# WBH2.net
KiCad netlist of a schematic drawn in EAGLE
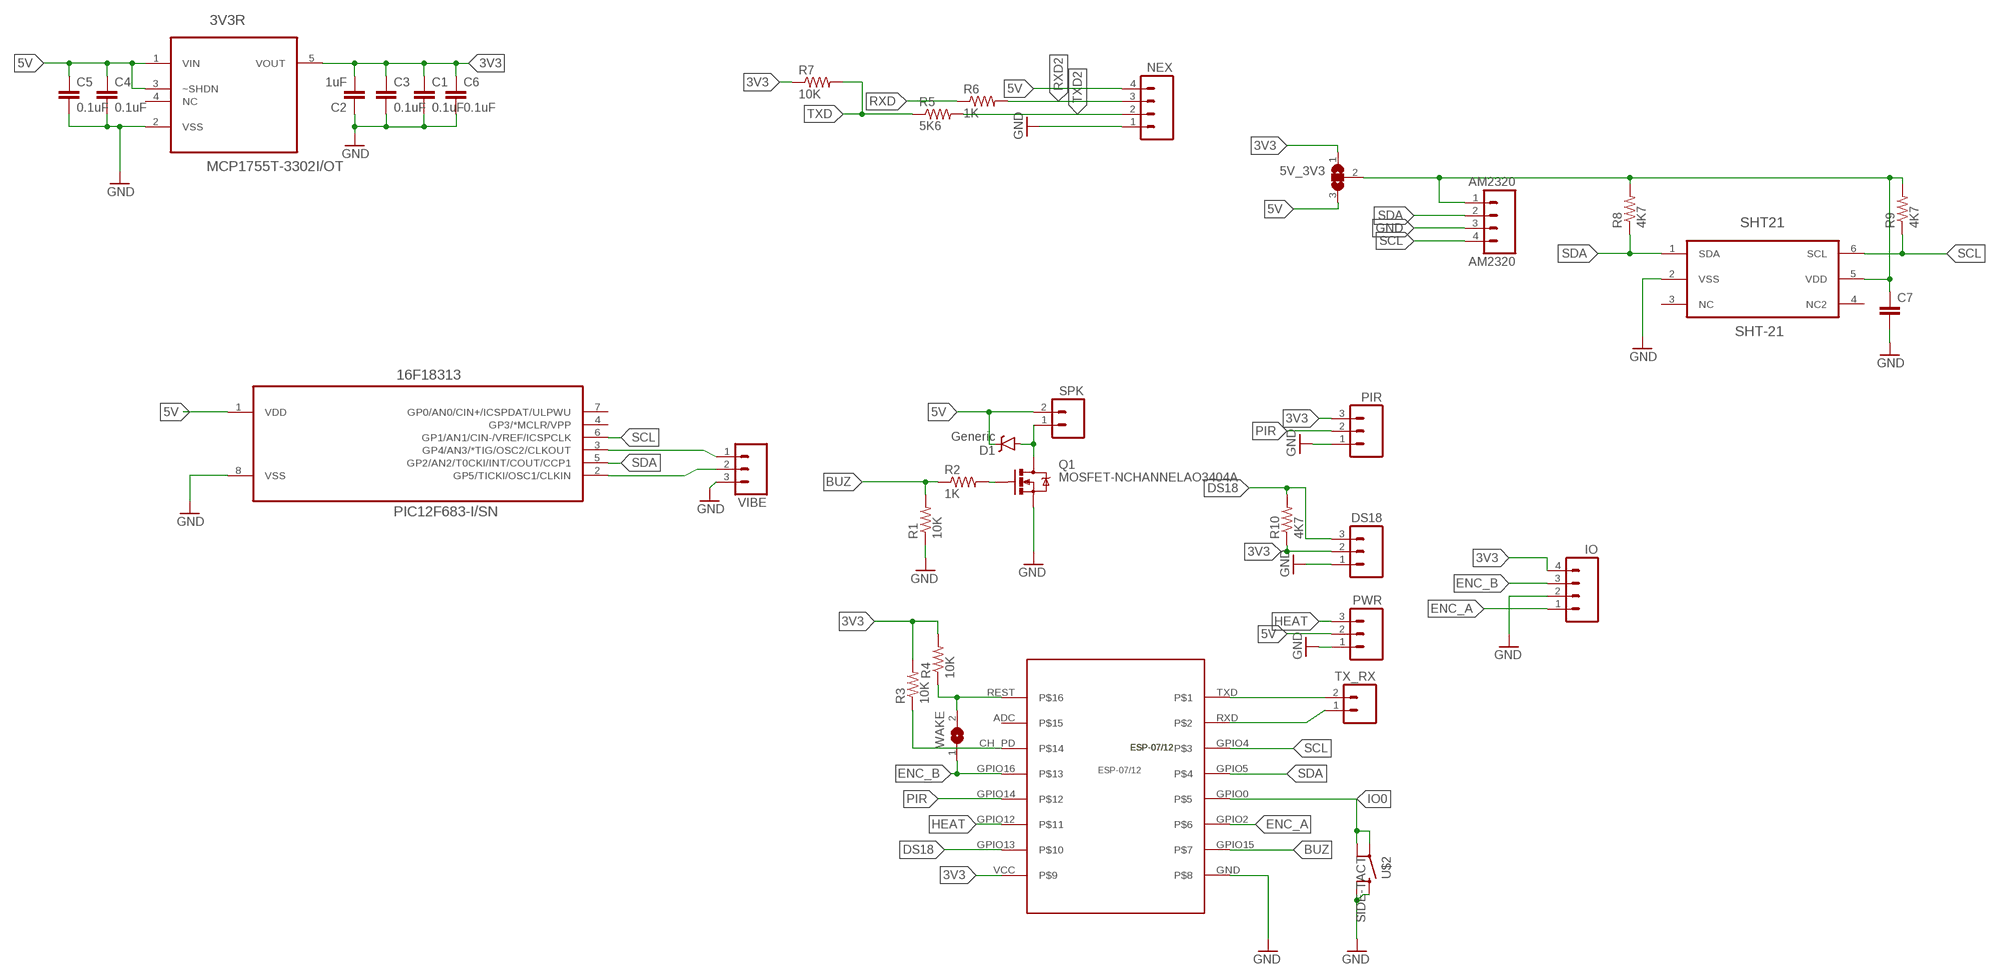
[diagram p0: schematic, sheet 1]

(export (version "E")
  (design (tool "Eeschema 10.0.6"))
  (components
    (comp (ref "3V3R")
      (value "MCP1755T-3302I/OT")
      (footprint "eagle-import:SOT95P270X145-5N")
      (fields (field (name "MPN") "MCP1801T-3302I/OT"))
      (libsource (lib "eagle-import") (part "MCP1801T-3302I/OT"))
    )
    (comp (ref "5V_3V3")
      (value "SJ2W")
      (footprint "eagle-import:SJ_2")
      (libsource (lib "eagle-import") (part "SJ2W"))
    )
    (comp (ref "16F18313")
      (value "PIC12F683-I/SN")
      (footprint "eagle-import:SOIC127P600X175-8N")
      (libsource (lib "eagle-import") (part "PIC12F683-I/SN"))
    )
    (comp (ref "AM2320")
      (value "AM2320")
      (footprint "eagle-import:1X04")
      (libsource (lib "eagle-import") (part "M04PTH"))
    )
    (comp (ref "C1")
      (value "0.1uF")
      (footprint "eagle-import:0805")
      (libsource (lib "eagle-import") (part "CAP0805"))
    )
    (comp (ref "C2")
      (value "1uF")
      (footprint "eagle-import:0805")
      (libsource (lib "eagle-import") (part "CAP0805"))
    )
    (comp (ref "C3")
      (value "0.1uF")
      (footprint "eagle-import:0805")
      (libsource (lib "eagle-import") (part "CAP0805"))
    )
    (comp (ref "C4")
      (value "0.1uF")
      (footprint "eagle-import:0805")
      (libsource (lib "eagle-import") (part "CAP0805"))
    )
    (comp (ref "C5")
      (value "0.1uF")
      (footprint "eagle-import:0805")
      (libsource (lib "eagle-import") (part "CAP0805"))
    )
    (comp (ref "C6")
      (value "0.1uF")
      (footprint "eagle-import:0805")
      (libsource (lib "eagle-import") (part "CAP0805"))
    )
    (comp (ref "C7")
      (value "CAP0603-CAP")
      (footprint "eagle-import:0603-CAP")
      (libsource (lib "eagle-import") (part "CAP0603-CAP"))
    )
    (comp (ref "D1")
      (value "Generic")
      (footprint "eagle-import:SOD-323")
      (libsource (lib "eagle-import") (part "DIODE-SCHOTTKY-BAT20J"))
    )
    (comp (ref "DS18")
      (value "M03PTH")
      (footprint "eagle-import:1X03")
      (libsource (lib "eagle-import") (part "M03PTH"))
    )
    (comp (ref "IO")
      (value "M04PTH")
      (footprint "eagle-import:1X04")
      (libsource (lib "eagle-import") (part "M04PTH"))
    )
    (comp (ref "NEX")
      (value "M04PTH")
      (footprint "eagle-import:1X04")
      (libsource (lib "eagle-import") (part "M04PTH"))
    )
    (comp (ref "PIR")
      (value "M03PTH")
      (footprint "eagle-import:1X03")
      (libsource (lib "eagle-import") (part "M03PTH"))
    )
    (comp (ref "PWR")
      (value "M03PTH")
      (footprint "eagle-import:1X03")
      (libsource (lib "eagle-import") (part "M03PTH"))
    )
    (comp (ref "Q1")
      (value "MOSFET-NCHANNELAO3404A")
      (footprint "eagle-import:SOT23-3")
      (libsource (lib "eagle-import") (part "MOSFET-NCHANNELAO3404A"))
    )
    (comp (ref "R1")
      (value "10K")
      (footprint "eagle-import:0805")
      (libsource (lib "eagle-import") (part "RESISTOR0805-RES"))
    )
    (comp (ref "R2")
      (value "1K")
      (footprint "eagle-import:0805")
      (libsource (lib "eagle-import") (part "RESISTOR0805-RES"))
    )
    (comp (ref "R3")
      (value "10K")
      (footprint "eagle-import:0805")
      (libsource (lib "eagle-import") (part "RESISTOR0805-RES"))
    )
    (comp (ref "R4")
      (value "10K")
      (footprint "eagle-import:0805")
      (libsource (lib "eagle-import") (part "RESISTOR0805-RES"))
    )
    (comp (ref "R5")
      (value "5K6")
      (footprint "eagle-import:0805")
      (libsource (lib "eagle-import") (part "RESISTOR0805-RES"))
    )
    (comp (ref "R6")
      (value "1K")
      (footprint "eagle-import:0805")
      (libsource (lib "eagle-import") (part "RESISTOR0805-RES"))
    )
    (comp (ref "R7")
      (value "10K")
      (footprint "eagle-import:0805")
      (libsource (lib "eagle-import") (part "RESISTOR0805-RES"))
    )
    (comp (ref "R8")
      (value "4K7")
      (footprint "eagle-import:0805")
      (libsource (lib "eagle-import") (part "RESISTOR0805-RES"))
    )
    (comp (ref "R9")
      (value "4K7")
      (footprint "eagle-import:0805")
      (libsource (lib "eagle-import") (part "RESISTOR0805-RES"))
    )
    (comp (ref "R10")
      (value "4K7")
      (footprint "eagle-import:0805")
      (libsource (lib "eagle-import") (part "RESISTOR0805-RES"))
    )
    (comp (ref "SHT21")
      (value "SHT-21")
      (footprint "eagle-import:SHT21")
      (libsource (lib "eagle-import") (part "SHT-21"))
    )
    (comp (ref "SPK")
      (value "M02PTH")
      (footprint "eagle-import:1X02")
      (libsource (lib "eagle-import") (part "M02PTH"))
    )
    (comp (ref "TX_RX")
      (value "M02PTH")
      (footprint "eagle-import:1X02")
      (libsource (lib "eagle-import") (part "M02PTH"))
    )
    (comp (ref "U$1")
      (value "ESP-07/12")
      (footprint "eagle-import:ESP-07_12")
      (libsource (lib "eagle-import") (part "ESP-07/12"))
    )
    (comp (ref "U$2")
      (value "SIDE-TACT")
      (footprint "eagle-import:SIDE-TACT")
      (libsource (lib "eagle-import") (part "SIDE-TACT"))
    )
    (comp (ref "VIBE")
      (value "M03PTH")
      (footprint "eagle-import:1X03")
      (libsource (lib "eagle-import") (part "M03PTH"))
    )
    (comp (ref "WAKE")
      (value "SJ")
      (footprint "eagle-import:SJ")
      (libsource (lib "eagle-import") (part "SJ"))
    )
  )
  (nets
    (net (code "1") (name "/NC") (class "Default")
      (node (ref "SHT21") (pin "3") (pinfunction "NC_3") (pintype "power_in"))
    )
    (net (code "2") (name "3V3") (class "Default")
      (node (ref "3V3R") (pin "5") (pinfunction "VOUT_5") (pintype "output"))
      (node (ref "5V_3V3") (pin "1") (pinfunction "1_1") (pintype "passive"))
      (node (ref "C1") (pin "1") (pinfunction "1_1") (pintype "passive"))
      (node (ref "C2") (pin "2") (pinfunction "2_2") (pintype "passive"))
      (node (ref "C3") (pin "1") (pinfunction "1_1") (pintype "passive"))
      (node (ref "C6") (pin "1") (pinfunction "1_1") (pintype "passive"))
      (node (ref "DS18") (pin "2") (pinfunction "2_2") (pintype "passive"))
      (node (ref "IO") (pin "4") (pinfunction "4_4") (pintype "passive"))
      (node (ref "PIR") (pin "3") (pinfunction "3_3") (pintype "passive"))
      (node (ref "R10") (pin "1") (pinfunction "1_1") (pintype "passive"))
      (node (ref "R3") (pin "2") (pinfunction "2_2") (pintype "passive"))
      (node (ref "R4") (pin "2") (pinfunction "2_2") (pintype "passive"))
      (node (ref "R7") (pin "1") (pinfunction "1_1") (pintype "passive"))
      (node (ref "U$1") (pin "VCC") (pinfunction "P$9_VCC") (pintype "bidirectional"))
    )
    (net (code "3") (name "5V") (class "Default")
      (node (ref "16F18313") (pin "1") (pinfunction "VDD_1") (pintype "power_in"))
      (node (ref "3V3R") (pin "1") (pinfunction "VIN_1") (pintype "power_in"))
      (node (ref "3V3R") (pin "3") (pinfunction "~{SHDN}_3") (pintype "input"))
      (node (ref "5V_3V3") (pin "3") (pinfunction "3_3") (pintype "passive"))
      (node (ref "C4") (pin "1") (pinfunction "1_1") (pintype "passive"))
      (node (ref "C5") (pin "1") (pinfunction "1_1") (pintype "passive"))
      (node (ref "D1") (pin "C") (pinfunction "C_C") (pintype "passive"))
      (node (ref "NEX") (pin "4") (pinfunction "4_4") (pintype "passive"))
      (node (ref "PWR") (pin "2") (pinfunction "2_2") (pintype "passive"))
      (node (ref "SPK") (pin "2") (pinfunction "2_2") (pintype "passive"))
    )
    (net (code "4") (name "BUZ") (class "Default")
      (node (ref "R1") (pin "2") (pinfunction "2_2") (pintype "passive"))
      (node (ref "R2") (pin "1") (pinfunction "1_1") (pintype "passive"))
      (node (ref "U$1") (pin "GPIO15") (pinfunction "P$7_GPIO15") (pintype "bidirectional"))
    )
    (net (code "5") (name "DS18") (class "Default")
      (node (ref "DS18") (pin "3") (pinfunction "3_3") (pintype "passive"))
      (node (ref "R10") (pin "2") (pinfunction "2_2") (pintype "passive"))
      (node (ref "U$1") (pin "GPIO13") (pinfunction "P$10_GPIO13") (pintype "bidirectional"))
    )
    (net (code "6") (name "ENC_A") (class "Default")
      (node (ref "IO") (pin "1") (pinfunction "1_1") (pintype "passive"))
      (node (ref "U$1") (pin "GPIO2") (pinfunction "P$6_GPIO2") (pintype "bidirectional"))
    )
    (net (code "7") (name "ENC_B") (class "Default")
      (node (ref "IO") (pin "3") (pinfunction "3_3") (pintype "passive"))
      (node (ref "U$1") (pin "GPIO16") (pinfunction "P$13_GPIO16") (pintype "bidirectional"))
      (node (ref "WAKE") (pin "1") (pinfunction "1_1") (pintype "passive"))
    )
    (net (code "8") (name "GND") (class "Default")
      (node (ref "16F18313") (pin "8") (pinfunction "VSS_8") (pintype "passive"))
      (node (ref "3V3R") (pin "2") (pinfunction "VSS_2") (pintype "passive"))
      (node (ref "AM2320") (pin "3") (pinfunction "3_3") (pintype "passive"))
      (node (ref "C1") (pin "2") (pinfunction "2_2") (pintype "passive"))
      (node (ref "C2") (pin "1") (pinfunction "1_1") (pintype "passive"))
      (node (ref "C3") (pin "2") (pinfunction "2_2") (pintype "passive"))
      (node (ref "C4") (pin "2") (pinfunction "2_2") (pintype "passive"))
      (node (ref "C5") (pin "2") (pinfunction "2_2") (pintype "passive"))
      (node (ref "C6") (pin "2") (pinfunction "2_2") (pintype "passive"))
      (node (ref "C7") (pin "2") (pinfunction "2_2") (pintype "passive"))
      (node (ref "DS18") (pin "1") (pinfunction "1_1") (pintype "passive"))
      (node (ref "IO") (pin "2") (pinfunction "2_2") (pintype "passive"))
      (node (ref "NEX") (pin "1") (pinfunction "1_1") (pintype "passive"))
      (node (ref "PIR") (pin "1") (pinfunction "1_1") (pintype "passive"))
      (node (ref "PWR") (pin "1") (pinfunction "1_1") (pintype "passive"))
      (node (ref "Q1") (pin "2") (pinfunction "S_2") (pintype "passive"))
      (node (ref "R1") (pin "1") (pinfunction "1_1") (pintype "passive"))
      (node (ref "SHT21") (pin "2") (pinfunction "VSS_2") (pintype "input"))
      (node (ref "U$1") (pin "GND") (pinfunction "P$8_GND") (pintype "bidirectional"))
      (node (ref "U$2") (pin "3") (pinfunction "2_3") (pintype "passive"))
      (node (ref "U$2") (pin "4") (pinfunction "4_4") (pintype "passive"))
      (node (ref "VIBE") (pin "3") (pinfunction "3_3") (pintype "passive"))
    )
    (net (code "9") (name "HEAT") (class "Default")
      (node (ref "PWR") (pin "3") (pinfunction "3_3") (pintype "passive"))
      (node (ref "U$1") (pin "GPIO12") (pinfunction "P$11_GPIO12") (pintype "bidirectional"))
    )
    (net (code "10") (name "IO0") (class "Default")
      (node (ref "U$1") (pin "GPIO0") (pinfunction "P$5_GPIO0") (pintype "bidirectional"))
      (node (ref "U$2") (pin "1") (pinfunction "1_1") (pintype "passive"))
      (node (ref "U$2") (pin "2") (pinfunction "3_2") (pintype "passive"))
    )
    (net (code "11") (name "Net-(16F18313-GP4{slash}AN3{slash}*TIG{slash}OSC2{slash}CLKOUT)") (class "Default")
      (node (ref "16F18313") (pin "3") (pinfunction "GP4/AN3/*TIG/OSC2/CLKOUT_3") (pintype "bidirectional"))
      (node (ref "VIBE") (pin "1") (pinfunction "1_1") (pintype "passive"))
    )
    (net (code "12") (name "Net-(16F18313-GP5{slash}TICKI{slash}OSC1{slash}CLKIN)") (class "Default")
      (node (ref "16F18313") (pin "2") (pinfunction "GP5/TICKI/OSC1/CLKIN_2") (pintype "bidirectional"))
      (node (ref "VIBE") (pin "2") (pinfunction "2_2") (pintype "passive"))
    )
    (net (code "13") (name "Net-(Q1-D)") (class "Default")
      (node (ref "D1") (pin "A") (pinfunction "A_A") (pintype "passive"))
      (node (ref "Q1") (pin "3") (pinfunction "D_3") (pintype "passive"))
      (node (ref "SPK") (pin "1") (pinfunction "1_1") (pintype "passive"))
    )
    (net (code "14") (name "Net-(Q1-G)") (class "Default")
      (node (ref "Q1") (pin "1") (pinfunction "G_1") (pintype "passive"))
      (node (ref "R2") (pin "2") (pinfunction "2_2") (pintype "passive"))
    )
    (net (code "15") (name "Net-(SHT21-VDD)") (class "Default")
      (node (ref "5V_3V3") (pin "2") (pinfunction "2_2") (pintype "passive"))
      (node (ref "AM2320") (pin "1") (pinfunction "1_1") (pintype "passive"))
      (node (ref "C7") (pin "1") (pinfunction "1_1") (pintype "passive"))
      (node (ref "R8") (pin "2") (pinfunction "2_2") (pintype "passive"))
      (node (ref "R9") (pin "2") (pinfunction "2_2") (pintype "passive"))
      (node (ref "SHT21") (pin "5") (pinfunction "VDD_5") (pintype "bidirectional"))
    )
    (net (code "16") (name "Net-(U$1-P$14)") (class "Default")
      (node (ref "R3") (pin "1") (pinfunction "1_1") (pintype "passive"))
      (node (ref "U$1") (pin "CH_PD") (pinfunction "P$14_CH_PD") (pintype "bidirectional"))
    )
    (net (code "17") (name "Net-(U$1-P$16)") (class "Default")
      (node (ref "R4") (pin "1") (pinfunction "1_1") (pintype "passive"))
      (node (ref "U$1") (pin "REST") (pinfunction "P$16_REST") (pintype "bidirectional"))
      (node (ref "WAKE") (pin "2") (pinfunction "2_2") (pintype "passive"))
    )
    (net (code "18") (name "PIR") (class "Default")
      (node (ref "PIR") (pin "2") (pinfunction "2_2") (pintype "passive"))
      (node (ref "U$1") (pin "GPIO14") (pinfunction "P$12_GPIO14") (pintype "bidirectional"))
    )
    (net (code "19") (name "RXD") (class "Default")
      (node (ref "R6") (pin "1") (pinfunction "1_1") (pintype "passive"))
      (node (ref "TX_RX") (pin "1") (pinfunction "1_1") (pintype "passive"))
      (node (ref "U$1") (pin "RXD") (pinfunction "P$2_RXD") (pintype "bidirectional"))
    )
    (net (code "20") (name "RXD2") (class "Default")
      (node (ref "NEX") (pin "3") (pinfunction "3_3") (pintype "passive"))
      (node (ref "R6") (pin "2") (pinfunction "2_2") (pintype "passive"))
    )
    (net (code "21") (name "SCL") (class "Default")
      (node (ref "16F18313") (pin "6") (pinfunction "GP1/AN1/CIN-/VREF/ICSPCLK_6") (pintype "bidirectional"))
      (node (ref "AM2320") (pin "4") (pinfunction "4_4") (pintype "passive"))
      (node (ref "R9") (pin "1") (pinfunction "1_1") (pintype "passive"))
      (node (ref "SHT21") (pin "6") (pinfunction "SCL_6") (pintype "bidirectional"))
      (node (ref "U$1") (pin "GPIO4") (pinfunction "P$3_GPIO4") (pintype "bidirectional"))
    )
    (net (code "22") (name "SDA") (class "Default")
      (node (ref "16F18313") (pin "5") (pinfunction "GP2/AN2/T0CKI/INT/COUT/CCP1_5") (pintype "bidirectional"))
      (node (ref "AM2320") (pin "2") (pinfunction "2_2") (pintype "passive"))
      (node (ref "R8") (pin "1") (pinfunction "1_1") (pintype "passive"))
      (node (ref "SHT21") (pin "1") (pinfunction "SDA_1") (pintype "power_in"))
      (node (ref "U$1") (pin "GPIO5") (pinfunction "P$4_GPIO5") (pintype "bidirectional"))
    )
    (net (code "23") (name "TXD") (class "Default")
      (node (ref "R5") (pin "1") (pinfunction "1_1") (pintype "passive"))
      (node (ref "R7") (pin "2") (pinfunction "2_2") (pintype "passive"))
      (node (ref "TX_RX") (pin "2") (pinfunction "2_2") (pintype "passive"))
      (node (ref "U$1") (pin "TXD") (pinfunction "P$1_TXD") (pintype "bidirectional"))
    )
    (net (code "24") (name "TXD2") (class "Default")
      (node (ref "NEX") (pin "2") (pinfunction "2_2") (pintype "passive"))
      (node (ref "R5") (pin "2") (pinfunction "2_2") (pintype "passive"))
    )
    (net (code "25") (name "unconnected-(3V3R-NC-Pad4)") (class "Default")
      (node (ref "3V3R") (pin "4") (pinfunction "NC_4") (pintype "no_connect"))
    )
    (net (code "26") (name "unconnected-(16F18313-GP0{slash}AN0{slash}CIN+{slash}ICSPDAT{slash}ULPWU-Pad7)") (class "Default")
      (node (ref "16F18313") (pin "7") (pinfunction "GP0/AN0/CIN+/ICSPDAT/ULPWU_7") (pintype "bidirectional"))
    )
    (net (code "27") (name "unconnected-(16F18313-GP3{slash}*MCLR{slash}VPP-Pad4)") (class "Default")
      (node (ref "16F18313") (pin "4") (pinfunction "GP3/*MCLR/VPP_4") (pintype "bidirectional"))
    )
    (net (code "28") (name "unconnected-(SHT21-NC2-Pad4)") (class "Default")
      (node (ref "SHT21") (pin "4") (pinfunction "NC2_4") (pintype "bidirectional"))
    )
    (net (code "29") (name "unconnected-(U$1-P$15-PadADC)") (class "Default")
      (node (ref "U$1") (pin "ADC") (pinfunction "P$15_ADC") (pintype "bidirectional"))
    )
  )
)
